# 1117_3_3V.net
KiCad netlist of a schematic drawn in EAGLE
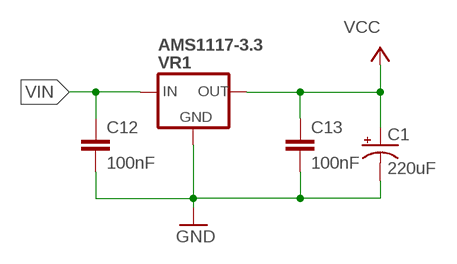
[diagram p0: schematic, sheet 1]

(export (version "E")
  (design (tool "Eeschema 10.0.6"))
  (components
    (comp (ref "C1")
      (value "220uF")
      (footprint "eagle-import:UD-6,3X7,7_NICHICON")
      (libsource (lib "eagle-import") (part "CPOL-USUD-6,3X7,7"))
    )
    (comp (ref "C12")
      (value "100nF")
      (footprint "eagle-import:C0805")
      (libsource (lib "eagle-import") (part "C-EUC0805"))
    )
    (comp (ref "C13")
      (value "100nF")
      (footprint "eagle-import:C0805")
      (libsource (lib "eagle-import") (part "C-EUC0805"))
    )
    (comp (ref "VR1")
      (value "AMS1117-3.3")
      (footprint "eagle-import:SOT223")
      (libsource (lib "eagle-import") (part "NCP1117ST50T3G"))
    )
  )
  (nets
    (net (code "1") (name "GND") (class "Default")
      (node (ref "C1") (pin "-") (pinfunction "-_-") (pintype "passive"))
      (node (ref "C12") (pin "2") (pinfunction "2_2") (pintype "passive"))
      (node (ref "C13") (pin "2") (pinfunction "2_2") (pintype "passive"))
      (node (ref "VR1") (pin "1") (pinfunction "GND_1") (pintype "input"))
    )
    (net (code "2") (name "VCC") (class "Default")
      (node (ref "C1") (pin "+") (pinfunction "+_+") (pintype "passive"))
      (node (ref "C13") (pin "1") (pinfunction "1_1") (pintype "passive"))
      (node (ref "VR1") (pin "2") (pinfunction "OUT_2") (pintype "output"))
      (node (ref "VR1") (pin "4") (pinfunction "OUT_4") (pintype "output"))
    )
    (net (code "3") (name "VIN") (class "Default")
      (node (ref "C12") (pin "1") (pinfunction "1_1") (pintype "passive"))
      (node (ref "VR1") (pin "3") (pinfunction "IN_3") (pintype "input"))
    )
  )
)
